# led_bar.net
KiCad netlist of a schematic drawn in EAGLE
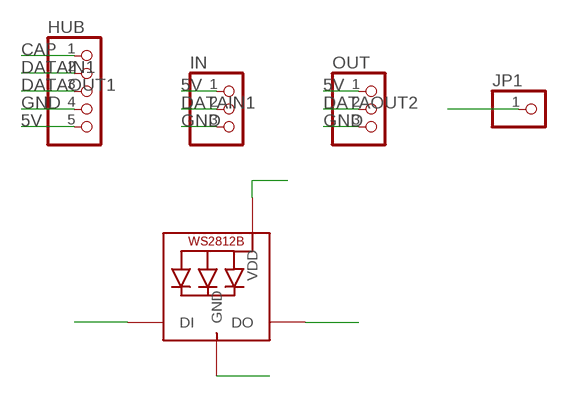
[diagram p0: schematic, sheet 1]

(export (version "E")
  (design (tool "Eeschema 10.0.6"))
  (components
    (comp (ref "HUB")
      (value "PINHD-1X5")
      (footprint "eagle-import:1X05")
      (libsource (lib "eagle-import") (part "PINHD-1X5"))
    )
    (comp (ref "IN")
      (value "PINHD-1X3")
      (footprint "eagle-import:1X03")
      (libsource (lib "eagle-import") (part "PINHD-1X3"))
    )
    (comp (ref "JP1")
      (value "PINHD-1X1")
      (footprint "eagle-import:1X01")
      (libsource (lib "eagle-import") (part "PINHD-1X1"))
    )
    (comp (ref "LED1")
      (value "WS2812B5050")
      (footprint "eagle-import:WS2812B")
      (libsource (lib "eagle-import") (part "WS2812B5050"))
    )
    (comp (ref "OUT")
      (value "PINHD-1X3")
      (footprint "eagle-import:1X03")
      (libsource (lib "eagle-import") (part "PINHD-1X3"))
    )
  )
  (nets
    (net (code "1") (name "/5V") (class "Default")
      (node (ref "HUB") (pin "5") (pinfunction "5_5") (pintype "passive"))
      (node (ref "IN") (pin "1") (pinfunction "1_1") (pintype "passive"))
      (node (ref "LED1") (pin "1-VDD") (pinfunction "VDD_1-VDD") (pintype "power_in"))
      (node (ref "OUT") (pin "1") (pinfunction "1_1") (pintype "passive"))
    )
    (net (code "2") (name "/CAP") (class "Default")
      (node (ref "HUB") (pin "1") (pinfunction "1_1") (pintype "passive"))
    )
    (net (code "3") (name "/DATAIN1") (class "Default")
      (node (ref "HUB") (pin "2") (pinfunction "2_2") (pintype "passive"))
      (node (ref "IN") (pin "2") (pinfunction "2_2") (pintype "passive"))
      (node (ref "LED1") (pin "4-DIN") (pinfunction "DI_4-DIN") (pintype "input"))
    )
    (net (code "4") (name "/DATAOUT1") (class "Default")
      (node (ref "HUB") (pin "3") (pinfunction "3_3") (pintype "passive"))
      (node (ref "JP1") (pin "1") (pinfunction "1_1") (pintype "passive"))
    )
    (net (code "5") (name "/DATAOUT2") (class "Default")
      (node (ref "LED1") (pin "2-DOUT") (pinfunction "DO_2-DOUT") (pintype "output"))
      (node (ref "OUT") (pin "2") (pinfunction "2_2") (pintype "passive"))
    )
    (net (code "6") (name "/GND") (class "Default")
      (node (ref "HUB") (pin "4") (pinfunction "4_4") (pintype "passive"))
      (node (ref "IN") (pin "3") (pinfunction "3_3") (pintype "passive"))
      (node (ref "LED1") (pin "3-GND") (pinfunction "GND_3-GND") (pintype "power_in"))
      (node (ref "OUT") (pin "3") (pinfunction "3_3") (pintype "passive"))
    )
  )
)
